# Power.net
KiCad netlist of a schematic drawn in Altium Designer
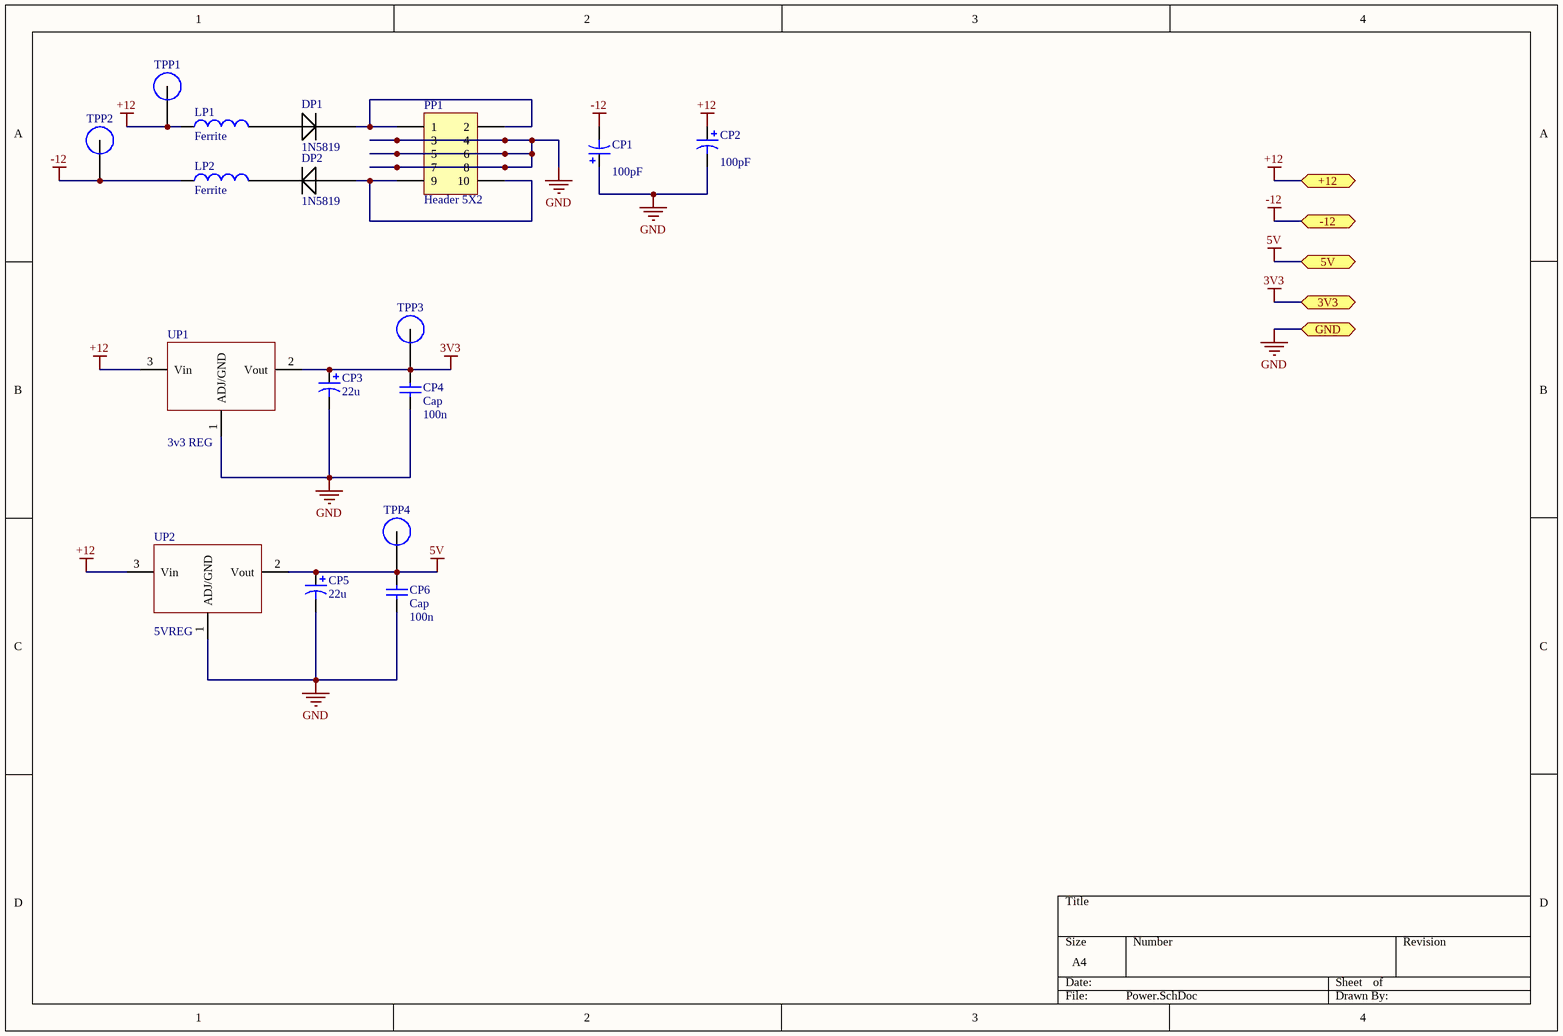
[diagram p0: Power.SchDoc]

(export (version "E")
  (design (tool "Eeschema 10.0.6"))
  (components
    (comp (ref "CP1")
      (value "100pF")
      (footprint "C-RAD-4.5")
      (description "Polarized Capacitor (Axial)")
      (fields (field (name "Comment") "Cap Pol2") (field (name "PUBLISHER") "Altium Limited"))
      (libsource (lib "Standard") (part "Cap Pol2"))
    )
    (comp (ref "CP2")
      (value "100pF")
      (footprint "C-RAD-4.5")
      (description "Polarized Capacitor (Axial)")
      (fields (field (name "Comment") "Cap Pol2") (field (name "PUBLISHER") "Altium Limited"))
      (libsource (lib "Standard") (part "Cap Pol2"))
    )
    (comp (ref "CP3")
      (value "22u")
      (footprint "C 0603 / 1608")
      (description "Polarized Capacitor (Axial)")
      (fields (field (name "Comment") "Cap Pol2") (field (name "PUBLISHER") "Altium Limited"))
      (libsource (lib "Standard") (part "Cap Pol2"))
    )
    (comp (ref "CP4")
      (value "Cap")
      (footprint "C 0603 / 1608")
      (description "Capacitor")
      (fields (field (name "ALTIUM_VALUE") "100n") (field (name "PUBLISHER") "Altium Limited"))
      (libsource (lib "Standard") (part "Cap"))
    )
    (comp (ref "CP5")
      (value "22u")
      (footprint "C 0603 / 1608")
      (description "Polarized Capacitor (Axial)")
      (fields (field (name "Comment") "Cap Pol2") (field (name "PUBLISHER") "Altium Limited"))
      (libsource (lib "Standard") (part "Cap Pol2"))
    )
    (comp (ref "CP6")
      (value "Cap")
      (footprint "C 0603 / 1608")
      (description "Capacitor")
      (fields (field (name "ALTIUM_VALUE") "100n") (field (name "PUBLISHER") "Altium Limited"))
      (libsource (lib "Standard") (part "Cap"))
    )
    (comp (ref "DP1") (value "1N5819") (footprint "DO-41") (libsource (lib "Standard") (part "Diode")))
    (comp (ref "DP2") (value "1N5819") (footprint "DO-41") (libsource (lib "Standard") (part "Diode")))
    (comp (ref "LP1")
      (value "Ferrite")
      (footprint "RES0805R")
      (fields (field (name "PUBLISHER") "Altium Limited"))
      (libsource (lib "Miscellaneous Devices") (part "Inductor"))
    )
    (comp (ref "LP2")
      (value "Ferrite")
      (footprint "RES0805R")
      (description "Inductor")
      (fields (field (name "PUBLISHER") "Altium Limited"))
      (libsource (lib "Miscellaneous Devices") (part "Inductor"))
    )
    (comp (ref "PP1")
      (value "Header 5X2")
      (footprint "HDR2X5")
      (description "Header, 5-Pin, Dual row")
      (fields (field (name "PUBLISHER") "Altium Limited"))
      (libsource (lib "Miscellaneous Connectors") (part "Header 5X2"))
    )
    (comp (ref "TPP1")
      (value "Test Point")
      (footprint "Test POint")
      (libsource (lib "Standard") (part "Test Point"))
    )
    (comp (ref "TPP2")
      (value "Test Point")
      (footprint "Test POint")
      (libsource (lib "Standard") (part "Test Point"))
    )
    (comp (ref "TPP3")
      (value "Test Point")
      (footprint "Test POint")
      (libsource (lib "Standard") (part "Test Point"))
    )
    (comp (ref "TPP4")
      (value "Test Point")
      (footprint "Test POint")
      (libsource (lib "Standard") (part "Test Point"))
    )
    (comp (ref "UP1")
      (value "3v3 REG")
      (footprint "SOT-223-3 - REG")
      (description "LDO 3.3V/5V/12V")
      (libsource (lib "IC") (part "AMS1117"))
    )
    (comp (ref "UP2")
      (value "5VREG")
      (footprint "SOT-223-3 - REG")
      (description "LDO 3.3V/5V/12V")
      (libsource (lib "IC") (part "AMS1117"))
    )
  )
  (nets
    (net (code "1") (name "+12") (class "Default")
      (node (ref "CP2") (pin "1") (pinfunction "1_1") (pintype "passive"))
      (node (ref "LP1") (pin "1") (pinfunction "1_1") (pintype "passive"))
      (node (ref "TPP1") (pin "1") (pintype "passive"))
      (node (ref "UP1") (pin "3") (pinfunction "Vin_3") (pintype "passive"))
      (node (ref "UP2") (pin "3") (pinfunction "Vin_3") (pintype "passive"))
    )
    (net (code "2") (name "-12") (class "Default")
      (node (ref "CP1") (pin "2") (pinfunction "2_2") (pintype "passive"))
      (node (ref "LP2") (pin "1") (pinfunction "1_1") (pintype "passive"))
      (node (ref "TPP2") (pin "1") (pintype "passive"))
    )
    (net (code "3") (name "3V3") (class "Default")
      (node (ref "CP3") (pin "1") (pinfunction "1_1") (pintype "passive"))
      (node (ref "CP4") (pin "2") (pinfunction "2_2") (pintype "passive"))
      (node (ref "TPP3") (pin "1") (pintype "passive"))
      (node (ref "UP1") (pin "2") (pinfunction "Vout_2") (pintype "passive"))
    )
    (net (code "4") (name "5V") (class "Default")
      (node (ref "CP5") (pin "1") (pinfunction "1_1") (pintype "passive"))
      (node (ref "CP6") (pin "2") (pinfunction "2_2") (pintype "passive"))
      (node (ref "TPP4") (pin "1") (pintype "passive"))
      (node (ref "UP2") (pin "2") (pinfunction "Vout_2") (pintype "passive"))
    )
    (net (code "5") (name "GND") (class "Default")
      (node (ref "CP1") (pin "1") (pinfunction "1_1") (pintype "passive"))
      (node (ref "CP2") (pin "2") (pinfunction "2_2") (pintype "passive"))
      (node (ref "CP3") (pin "2") (pinfunction "2_2") (pintype "passive"))
      (node (ref "CP4") (pin "1") (pinfunction "1_1") (pintype "passive"))
      (node (ref "CP5") (pin "2") (pinfunction "2_2") (pintype "passive"))
      (node (ref "CP6") (pin "1") (pinfunction "1_1") (pintype "passive"))
      (node (ref "PP1") (pin "3") (pinfunction "3_3") (pintype "passive"))
      (node (ref "PP1") (pin "4") (pinfunction "4_4") (pintype "passive"))
      (node (ref "PP1") (pin "5") (pinfunction "5_5") (pintype "passive"))
      (node (ref "PP1") (pin "6") (pinfunction "6_6") (pintype "passive"))
      (node (ref "PP1") (pin "7") (pinfunction "7_7") (pintype "passive"))
      (node (ref "PP1") (pin "8") (pinfunction "8_8") (pintype "passive"))
      (node (ref "UP1") (pin "1") (pinfunction "ADJ/GND_1") (pintype "passive"))
      (node (ref "UP2") (pin "1") (pinfunction "ADJ/GND_1") (pintype "passive"))
    )
    (net (code "6") (name "Net-(DP1-Pad1)") (class "Default")
      (node (ref "DP1") (pin "1") (pinfunction "1_1") (pintype "passive"))
      (node (ref "PP1") (pin "1") (pinfunction "1_1") (pintype "passive"))
      (node (ref "PP1") (pin "2") (pinfunction "2_2") (pintype "passive"))
    )
    (net (code "7") (name "Net-(DP1-Pad2)") (class "Default")
      (node (ref "DP1") (pin "2") (pinfunction "2_2") (pintype "passive"))
      (node (ref "LP1") (pin "2") (pinfunction "2_2") (pintype "passive"))
    )
    (net (code "8") (name "Net-(DP2-Pad1)") (class "Default")
      (node (ref "DP2") (pin "1") (pinfunction "1_1") (pintype "passive"))
      (node (ref "LP2") (pin "2") (pinfunction "2_2") (pintype "passive"))
    )
    (net (code "9") (name "Net-(DP2-Pad2)") (class "Default")
      (node (ref "DP2") (pin "2") (pinfunction "2_2") (pintype "passive"))
      (node (ref "PP1") (pin "10") (pinfunction "10_10") (pintype "passive"))
      (node (ref "PP1") (pin "9") (pinfunction "9_9") (pintype "passive"))
    )
  )
)
